# uSD_shield.net
KiCad netlist of a schematic drawn in EAGLE
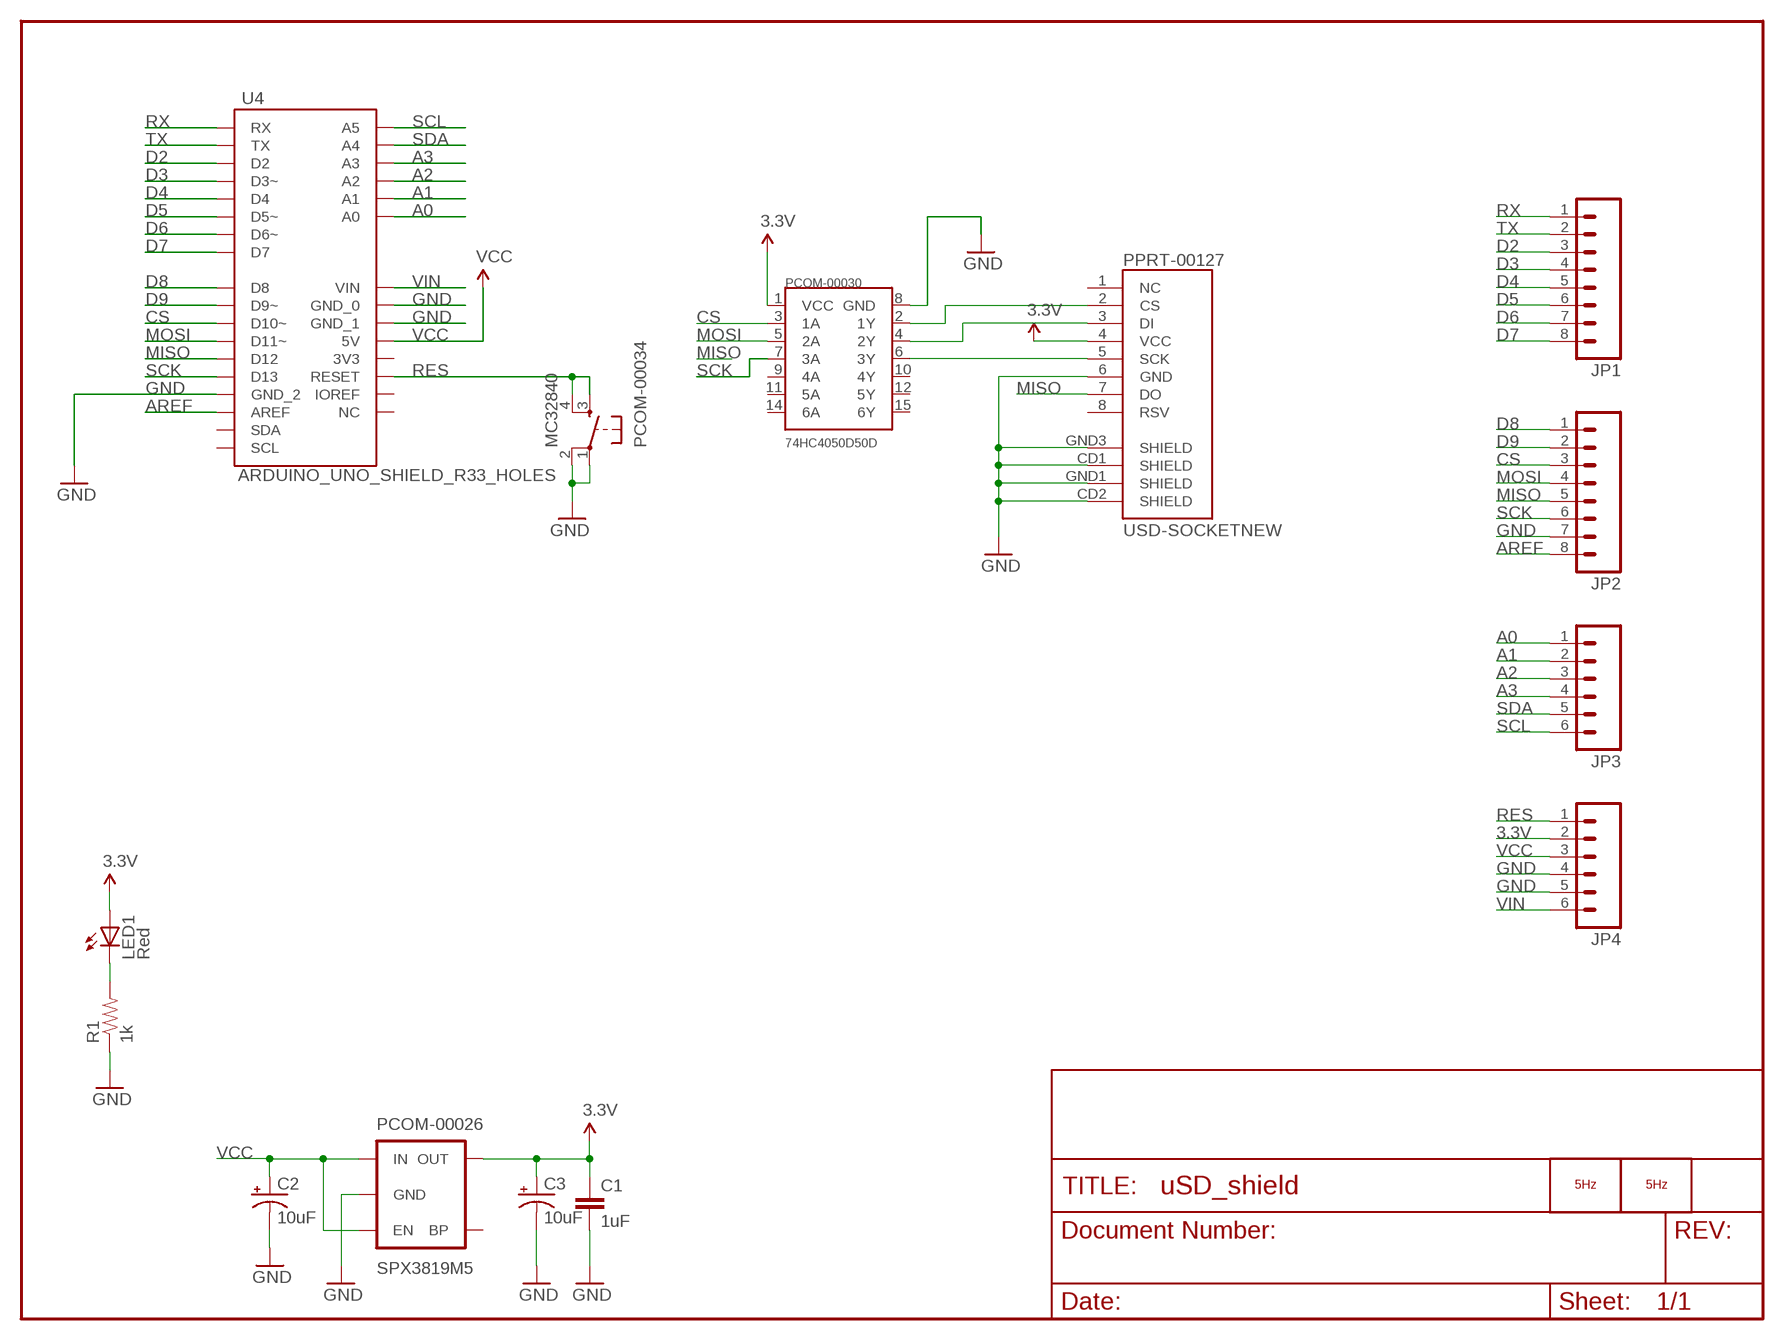
[diagram p0: schematic, sheet 1]

(export (version "E")
  (design (tool "Eeschema 10.0.6"))
  (components
    (comp (ref "C1")
      (value "1uF")
      (footprint "eagle-import:0603-CAP")
      (libsource (lib "eagle-import") (part "CAP0603-CAP"))
    )
    (comp (ref "C2")
      (value "10uF")
      (footprint "eagle-import:EIA3216")
      (libsource (lib "eagle-import") (part "CAP_POL1206"))
    )
    (comp (ref "C3")
      (value "10uF")
      (footprint "eagle-import:EIA3216")
      (libsource (lib "eagle-import") (part "CAP_POL1206"))
    )
    (comp (ref "JP1")
      (value "M08")
      (footprint "eagle-import:1X08")
      (libsource (lib "eagle-import") (part "M08"))
    )
    (comp (ref "JP2")
      (value "M08")
      (footprint "eagle-import:1X08")
      (libsource (lib "eagle-import") (part "M08"))
    )
    (comp (ref "JP3")
      (value "M06SIP")
      (footprint "eagle-import:1X06")
      (libsource (lib "eagle-import") (part "M06SIP"))
    )
    (comp (ref "JP4")
      (value "M06SIP")
      (footprint "eagle-import:1X06")
      (libsource (lib "eagle-import") (part "M06SIP"))
    )
    (comp (ref "LED1")
      (value "Red")
      (footprint "eagle-import:LED-0603")
      (libsource (lib "eagle-import") (part "LED0603"))
    )
    (comp (ref "LOGO2")
      (value "LOGO_5HZ_MAIN_10MM")
      (footprint "eagle-import:5HZ_LOGO_MAIN_10MM")
      (libsource (lib "eagle-import") (part "LOGO_5HZ_MAIN_10MM"))
    )
    (comp (ref "LOGO3")
      (value "LOGO_5HZ_H_COOPER_15MM")
      (footprint "eagle-import:5HZ_LOGO_H_COOPER_15MM")
      (libsource (lib "eagle-import") (part "LOGO_5HZ_H_COOPER_15MM"))
    )
    (comp (ref "PCOM-00026")
      (value "SPX3819M5")
      (footprint "eagle-import:SOT23-5")
      (libsource (lib "eagle-import") (part "V_REG_LDOSMD"))
    )
    (comp (ref "PCOM-00030")
      (value "74HC4050D50D")
      (footprint "eagle-import:SO016")
      (libsource (lib "eagle-import") (part "HEX_CONVERTER"))
    )
    (comp (ref "PCOM-00034")
      (value "MC32840")
      (footprint "eagle-import:TACTILE_SWITCH_SMD")
      (libsource (lib "eagle-import") (part "TAC_SWITCHSMD"))
    )
    (comp (ref "PPRT-00127")
      (value "USD-SOCKETNEW")
      (footprint "eagle-import:MICRO-SD-SOCKET-PP")
      (libsource (lib "eagle-import") (part "USD-SOCKETNEW"))
    )
    (comp (ref "R1")
      (value "1k")
      (footprint "eagle-import:0603-RES")
      (libsource (lib "eagle-import") (part "RESISTOR0603-RES"))
    )
    (comp (ref "U4")
      (value "ARDUINO_UNO_SHIELD_R33_HOLES")
      (footprint "eagle-import:UNO_R3_SHIELD_3_HOLES_NO_SILK")
      (libsource (lib "eagle-import") (part "ARDUINO_UNO_SHIELD_R33_HOLES"))
    )
  )
  (nets
    (net (code "1") (name "/A0") (class "Default")
      (node (ref "JP3") (pin "1") (pinfunction "1_1") (pintype "passive"))
      (node (ref "U4") (pin "A0") (pinfunction "A0_A0") (pintype "bidirectional"))
    )
    (net (code "2") (name "/A1") (class "Default")
      (node (ref "JP3") (pin "2") (pinfunction "2_2") (pintype "passive"))
      (node (ref "U4") (pin "A1") (pinfunction "A1_A1") (pintype "bidirectional"))
    )
    (net (code "3") (name "/A2") (class "Default")
      (node (ref "JP3") (pin "3") (pinfunction "3_3") (pintype "passive"))
      (node (ref "U4") (pin "A2") (pinfunction "A2_A2") (pintype "bidirectional"))
    )
    (net (code "4") (name "/A3") (class "Default")
      (node (ref "JP3") (pin "4") (pinfunction "4_4") (pintype "passive"))
      (node (ref "U4") (pin "A3") (pinfunction "A3_A3") (pintype "bidirectional"))
    )
    (net (code "5") (name "/AREF") (class "Default")
      (node (ref "JP2") (pin "8") (pinfunction "8_8") (pintype "passive"))
      (node (ref "U4") (pin "AREF") (pinfunction "AREF_AREF") (pintype "bidirectional"))
    )
    (net (code "6") (name "/CS") (class "Default")
      (node (ref "JP2") (pin "3") (pinfunction "3_3") (pintype "passive"))
      (node (ref "PCOM-00030") (pin "3") (pinfunction "1A_3") (pintype "bidirectional"))
      (node (ref "U4") (pin "D10") (pinfunction "D10~{}_D10") (pintype "bidirectional"))
    )
    (net (code "7") (name "/D2") (class "Default")
      (node (ref "JP1") (pin "3") (pinfunction "3_3") (pintype "passive"))
      (node (ref "U4") (pin "D2") (pinfunction "D2_D2") (pintype "bidirectional"))
    )
    (net (code "8") (name "/D3") (class "Default")
      (node (ref "JP1") (pin "4") (pinfunction "4_4") (pintype "passive"))
      (node (ref "U4") (pin "D3") (pinfunction "D3~{}_D3") (pintype "bidirectional"))
    )
    (net (code "9") (name "/D4") (class "Default")
      (node (ref "JP1") (pin "5") (pinfunction "5_5") (pintype "passive"))
      (node (ref "U4") (pin "D4") (pinfunction "D4_D4") (pintype "bidirectional"))
    )
    (net (code "10") (name "/D5") (class "Default")
      (node (ref "JP1") (pin "6") (pinfunction "6_6") (pintype "passive"))
      (node (ref "U4") (pin "D5") (pinfunction "D5~{}_D5") (pintype "bidirectional"))
    )
    (net (code "11") (name "/D6") (class "Default")
      (node (ref "JP1") (pin "7") (pinfunction "7_7") (pintype "passive"))
      (node (ref "U4") (pin "D6") (pinfunction "D6~{}_D6") (pintype "bidirectional"))
    )
    (net (code "12") (name "/D7") (class "Default")
      (node (ref "JP1") (pin "8") (pinfunction "8_8") (pintype "passive"))
      (node (ref "U4") (pin "D7") (pinfunction "D7_D7") (pintype "bidirectional"))
    )
    (net (code "13") (name "/D8") (class "Default")
      (node (ref "JP2") (pin "1") (pinfunction "1_1") (pintype "passive"))
      (node (ref "U4") (pin "D8") (pinfunction "D8_D8") (pintype "bidirectional"))
    )
    (net (code "14") (name "/D9") (class "Default")
      (node (ref "JP2") (pin "2") (pinfunction "2_2") (pintype "passive"))
      (node (ref "U4") (pin "D9") (pinfunction "D9~{}_D9") (pintype "bidirectional"))
    )
    (net (code "15") (name "/MISO") (class "Default")
      (node (ref "JP2") (pin "5") (pinfunction "5_5") (pintype "passive"))
      (node (ref "PPRT-00127") (pin "7") (pinfunction "DO_7") (pintype "bidirectional"))
      (node (ref "U4") (pin "D12") (pinfunction "D12_D12") (pintype "bidirectional"))
    )
    (net (code "16") (name "/MOSI") (class "Default")
      (node (ref "JP2") (pin "4") (pinfunction "4_4") (pintype "passive"))
      (node (ref "PCOM-00030") (pin "5") (pinfunction "2A_5") (pintype "bidirectional"))
      (node (ref "U4") (pin "D11") (pinfunction "D11~{}_D11") (pintype "bidirectional"))
    )
    (net (code "17") (name "/RES") (class "Default")
      (node (ref "JP4") (pin "1") (pinfunction "1_1") (pintype "passive"))
      (node (ref "PCOM-00034") (pin "3") (pinfunction "3_3") (pintype "passive"))
      (node (ref "PCOM-00034") (pin "4") (pinfunction "4_4") (pintype "passive"))
      (node (ref "U4") (pin "RES") (pinfunction "RESET_RES") (pintype "bidirectional"))
    )
    (net (code "18") (name "/RX") (class "Default")
      (node (ref "JP1") (pin "1") (pinfunction "1_1") (pintype "passive"))
      (node (ref "U4") (pin "RX") (pinfunction "RX_RX") (pintype "bidirectional"))
    )
    (net (code "19") (name "/SCK") (class "Default")
      (node (ref "JP2") (pin "6") (pinfunction "6_6") (pintype "passive"))
      (node (ref "PCOM-00030") (pin "7") (pinfunction "3A_7") (pintype "bidirectional"))
      (node (ref "U4") (pin "D13") (pinfunction "D13_D13") (pintype "bidirectional"))
    )
    (net (code "20") (name "/SCL") (class "Default")
      (node (ref "JP3") (pin "6") (pinfunction "6_6") (pintype "passive"))
      (node (ref "U4") (pin "A5") (pinfunction "A5_A5") (pintype "bidirectional"))
    )
    (net (code "21") (name "/SDA") (class "Default")
      (node (ref "JP3") (pin "5") (pinfunction "5_5") (pintype "passive"))
      (node (ref "U4") (pin "A4") (pinfunction "A4_A4") (pintype "bidirectional"))
    )
    (net (code "22") (name "/TX") (class "Default")
      (node (ref "JP1") (pin "2") (pinfunction "2_2") (pintype "passive"))
      (node (ref "U4") (pin "TX") (pinfunction "TX_TX") (pintype "bidirectional"))
    )
    (net (code "23") (name "/VIN") (class "Default")
      (node (ref "JP4") (pin "6") (pinfunction "6_6") (pintype "passive"))
      (node (ref "U4") (pin "VIN") (pinfunction "VIN_VIN") (pintype "bidirectional"))
    )
    (net (code "24") (name "3.3V") (class "Default")
      (node (ref "C1") (pin "1") (pinfunction "1_1") (pintype "passive"))
      (node (ref "C3") (pin "A") (pinfunction "+_A") (pintype "passive"))
      (node (ref "JP4") (pin "2") (pinfunction "2_2") (pintype "passive"))
      (node (ref "LED1") (pin "A") (pinfunction "A_A") (pintype "passive"))
      (node (ref "PCOM-00026") (pin "5") (pinfunction "OUT_5") (pintype "passive"))
      (node (ref "PCOM-00030") (pin "1") (pinfunction "VCC_1") (pintype "bidirectional"))
      (node (ref "PPRT-00127") (pin "4") (pinfunction "VCC_4") (pintype "bidirectional"))
    )
    (net (code "25") (name "GND") (class "Default")
      (node (ref "C1") (pin "2") (pinfunction "2_2") (pintype "passive"))
      (node (ref "C2") (pin "C") (pinfunction "-_C") (pintype "passive"))
      (node (ref "C3") (pin "C") (pinfunction "-_C") (pintype "passive"))
      (node (ref "JP2") (pin "7") (pinfunction "7_7") (pintype "passive"))
      (node (ref "JP4") (pin "4") (pinfunction "4_4") (pintype "passive"))
      (node (ref "JP4") (pin "5") (pinfunction "5_5") (pintype "passive"))
      (node (ref "PCOM-00026") (pin "2") (pinfunction "GND_2") (pintype "input"))
      (node (ref "PCOM-00030") (pin "8") (pinfunction "GND_8") (pintype "bidirectional"))
      (node (ref "PCOM-00034") (pin "1") (pinfunction "1_1") (pintype "passive"))
      (node (ref "PCOM-00034") (pin "2") (pinfunction "2_2") (pintype "passive"))
      (node (ref "PPRT-00127") (pin "6") (pinfunction "GND_6") (pintype "bidirectional"))
      (node (ref "PPRT-00127") (pin "CD1") (pinfunction "SHIELD_CD1") (pintype "bidirectional"))
      (node (ref "PPRT-00127") (pin "CD2") (pinfunction "SHIELD_CD2") (pintype "bidirectional"))
      (node (ref "PPRT-00127") (pin "GND1") (pinfunction "SHIELD_GND1") (pintype "bidirectional"))
      (node (ref "PPRT-00127") (pin "GND3") (pinfunction "SHIELD_GND3") (pintype "bidirectional"))
      (node (ref "R1") (pin "1") (pinfunction "1_1") (pintype "passive"))
      (node (ref "U4") (pin "GND_0") (pinfunction "GND_0_GND_0") (pintype "bidirectional"))
      (node (ref "U4") (pin "GND_1") (pinfunction "GND_1_GND_1") (pintype "bidirectional"))
      (node (ref "U4") (pin "GND_2") (pinfunction "GND_2_GND_2") (pintype "bidirectional"))
    )
    (net (code "26") (name "Net-(LED1-PadC)") (class "Default")
      (node (ref "LED1") (pin "C") (pinfunction "C_C") (pintype "passive"))
      (node (ref "R1") (pin "2") (pinfunction "2_2") (pintype "passive"))
    )
    (net (code "27") (name "Net-(PCOM-00030-1Y)") (class "Default")
      (node (ref "PCOM-00030") (pin "2") (pinfunction "1Y_2") (pintype "bidirectional"))
      (node (ref "PPRT-00127") (pin "2") (pinfunction "CS_2") (pintype "bidirectional"))
    )
    (net (code "28") (name "Net-(PCOM-00030-2Y)") (class "Default")
      (node (ref "PCOM-00030") (pin "4") (pinfunction "2Y_4") (pintype "bidirectional"))
      (node (ref "PPRT-00127") (pin "3") (pinfunction "DI_3") (pintype "bidirectional"))
    )
    (net (code "29") (name "Net-(PCOM-00030-3Y)") (class "Default")
      (node (ref "PCOM-00030") (pin "6") (pinfunction "3Y_6") (pintype "bidirectional"))
      (node (ref "PPRT-00127") (pin "5") (pinfunction "SCK_5") (pintype "bidirectional"))
    )
    (net (code "30") (name "VCC") (class "Default")
      (node (ref "C2") (pin "A") (pinfunction "+_A") (pintype "passive"))
      (node (ref "JP4") (pin "3") (pinfunction "3_3") (pintype "passive"))
      (node (ref "PCOM-00026") (pin "1") (pinfunction "IN_1") (pintype "input"))
      (node (ref "PCOM-00026") (pin "3") (pinfunction "EN_3") (pintype "input"))
      (node (ref "U4") (pin "5V") (pinfunction "5V_5V") (pintype "bidirectional"))
    )
    (net (code "31") (name "unconnected-(PCOM-00026-BP-Pad4)") (class "Default")
      (node (ref "PCOM-00026") (pin "4") (pinfunction "BP_4") (pintype "input"))
    )
    (net (code "32") (name "unconnected-(PCOM-00030-4A-Pad9)") (class "Default")
      (node (ref "PCOM-00030") (pin "9") (pinfunction "4A_9") (pintype "bidirectional"))
    )
    (net (code "33") (name "unconnected-(PCOM-00030-4Y-Pad10)") (class "Default")
      (node (ref "PCOM-00030") (pin "10") (pinfunction "4Y_10") (pintype "bidirectional"))
    )
    (net (code "34") (name "unconnected-(PCOM-00030-5A-Pad11)") (class "Default")
      (node (ref "PCOM-00030") (pin "11") (pinfunction "5A_11") (pintype "bidirectional"))
    )
    (net (code "35") (name "unconnected-(PCOM-00030-5Y-Pad12)") (class "Default")
      (node (ref "PCOM-00030") (pin "12") (pinfunction "5Y_12") (pintype "bidirectional"))
    )
    (net (code "36") (name "unconnected-(PCOM-00030-6A-Pad14)") (class "Default")
      (node (ref "PCOM-00030") (pin "14") (pinfunction "6A_14") (pintype "bidirectional"))
    )
    (net (code "37") (name "unconnected-(PCOM-00030-6Y-Pad15)") (class "Default")
      (node (ref "PCOM-00030") (pin "15") (pinfunction "6Y_15") (pintype "bidirectional"))
    )
    (net (code "38") (name "unconnected-(PPRT-00127-NC-Pad1)") (class "Default")
      (node (ref "PPRT-00127") (pin "1") (pinfunction "NC_1") (pintype "bidirectional"))
    )
    (net (code "39") (name "unconnected-(PPRT-00127-RSV-Pad8)") (class "Default")
      (node (ref "PPRT-00127") (pin "8") (pinfunction "RSV_8") (pintype "bidirectional"))
    )
    (net (code "40") (name "unconnected-(U4-3V3-Pad3.3V)") (class "Default")
      (node (ref "U4") (pin "3.3V") (pinfunction "3V3_3.3V") (pintype "bidirectional"))
    )
    (net (code "41") (name "unconnected-(U4-PadIOREF)") (class "Default")
      (node (ref "U4") (pin "IOREF") (pinfunction "IOREF_IOREF") (pintype "bidirectional"))
    )
    (net (code "42") (name "unconnected-(U4-PadNC)") (class "Default")
      (node (ref "U4") (pin "NC") (pinfunction "NC_NC") (pintype "no_connect"))
    )
    (net (code "43") (name "unconnected-(U4-PadSCL)") (class "Default")
      (node (ref "U4") (pin "SCL") (pinfunction "SCL_SCL") (pintype "bidirectional"))
    )
    (net (code "44") (name "unconnected-(U4-PadSDA)") (class "Default")
      (node (ref "U4") (pin "SDA") (pinfunction "SDA_SDA") (pintype "bidirectional"))
    )
  )
)
